# Sheet1.net
KiCad netlist of a schematic drawn in Altium Designer
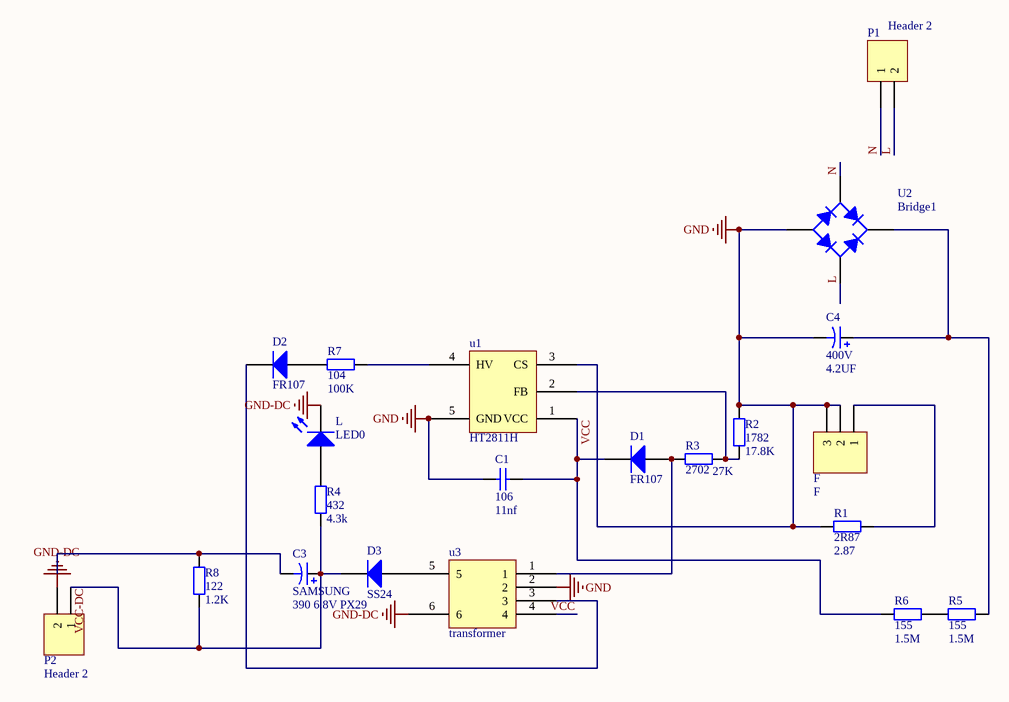
[diagram p0: Sheet1.SchDoc]

(export (version "E")
  (design (tool "Eeschema 10.0.6"))
  (components
    (comp (ref "C1")
      (value "106")
      (footprint "RAD-0.3")
      (description "Capacitor")
      (fields (field (name "ALTIUM_VALUE") "11nf") (field (name "PUBLISHER") "Altium Limited"))
      (libsource (lib "Miscellaneous Devices") (part "Cap"))
    )
    (comp (ref "C3")
      (value "SAMSUNG")
      (footprint "RB7.6-15")
      (description "Polarized Capacitor (Radial)")
      (fields (field (name "ALTIUM_VALUE") "390 6.8V PX29") (field (name "PUBLISHER") "Altium Limited"))
      (libsource (lib "Miscellaneous Devices") (part "Cap Pol1"))
    )
    (comp (ref "C4")
      (value "400V")
      (footprint "RB7.6-15")
      (description "Polarized Capacitor (Radial)")
      (fields (field (name "ALTIUM_VALUE") "4.2UF") (field (name "PUBLISHER") "Altium Limited"))
      (libsource (lib "Miscellaneous Devices") (part "Cap Pol1"))
    )
    (comp (ref "D1")
      (value "FR107")
      (footprint "LC-SOD-123F")
      (description "1 Amp General Purpose Rectifier")
      (fields (field (name "PUBLISHER") "Altium Limited"))
      (libsource (lib "Miscellaneous Devices") (part "Diode 1N4005"))
    )
    (comp (ref "D2")
      (value "FR107")
      (footprint "LC-SOD-123F")
      (description "1 Amp General Purpose Rectifier")
      (fields (field (name "PUBLISHER") "Altium Limited"))
      (libsource (lib "Miscellaneous Devices") (part "Diode 1N4005"))
    )
    (comp (ref "D3")
      (value "SS24")
      (footprint "LC-SMA(DO-214AC)_S1")
      (description "High Conductance Ultra Fast Diode")
      (fields (field (name "PUBLISHER") "Altium Limited"))
      (libsource (lib "Miscellaneous Devices") (part "Diode 1N4150"))
    )
    (comp (ref "F")
      (value "F")
      (footprint "HDR1X3")
      (description "Header, 3-Pin")
      (fields (field (name "PUBLISHER") "Altium Limited"))
      (libsource (lib "Miscellaneous Connectors") (part "Header 3"))
    )
    (comp (ref "L")
      (value "LED0")
      (footprint "LED-0")
      (description "Typical INFRARED GaAs LED")
      (fields (field (name "PUBLISHER") "Altium Limited"))
      (libsource (lib "Miscellaneous Devices") (part "LED0"))
    )
    (comp (ref "P1")
      (value "Header 2")
      (footprint "HDR1X2")
      (description "Header, 2-Pin")
      (fields (field (name "PUBLISHER") "Altium Limited"))
      (libsource (lib "") (part "Header 2_1"))
    )
    (comp (ref "P2")
      (value "Header 2")
      (footprint "HDR1X2")
      (description "Header, 2-Pin")
      (fields (field (name "PUBLISHER") "Altium Limited"))
      (libsource (lib "Miscellaneous Connectors") (part "Header 2"))
    )
    (comp (ref "R1")
      (value "2R87")
      (footprint "AXIAL-0.4")
      (description "Resistor")
      (fields (field (name "ALTIUM_VALUE") "2.87") (field (name "PUBLISHER") "Altium Limited"))
      (libsource (lib "") (part "Res2_1"))
    )
    (comp (ref "R2")
      (value "1782")
      (footprint "AXIAL-0.4")
      (description "Resistor")
      (fields (field (name "ALTIUM_VALUE") "17.8K") (field (name "PUBLISHER") "Altium Limited"))
      (libsource (lib "Miscellaneous Devices") (part "Res2"))
    )
    (comp (ref "R3")
      (value "2702")
      (footprint "AXIAL-0.4")
      (description "Resistor")
      (fields (field (name "ALTIUM_VALUE") "27K") (field (name "PUBLISHER") "Altium Limited"))
      (libsource (lib "") (part "Res2_3"))
    )
    (comp (ref "R4")
      (value "432")
      (footprint "AXIAL-0.4")
      (description "Resistor")
      (fields (field (name "ALTIUM_VALUE") "4.3k") (field (name "PUBLISHER") "Altium Limited"))
      (libsource (lib "Miscellaneous Devices") (part "Res2"))
    )
    (comp (ref "R5")
      (value "155")
      (footprint "AXIAL-0.4")
      (description "Resistor")
      (fields (field (name "ALTIUM_VALUE") "1.5M") (field (name "PUBLISHER") "Altium Limited"))
      (libsource (lib "") (part "Res2_1"))
    )
    (comp (ref "R6")
      (value "155")
      (footprint "AXIAL-0.4")
      (description "Resistor")
      (fields (field (name "ALTIUM_VALUE") "1.5M") (field (name "PUBLISHER") "Altium Limited"))
      (libsource (lib "") (part "Res2_1"))
    )
    (comp (ref "R7")
      (value "104")
      (footprint "AXIAL-0.4")
      (description "Resistor")
      (fields (field (name "ALTIUM_VALUE") "100K") (field (name "PUBLISHER") "Altium Limited"))
      (libsource (lib "") (part "Res2_1"))
    )
    (comp (ref "R8")
      (value "122")
      (footprint "AXIAL-0.4")
      (description "Resistor")
      (fields (field (name "ALTIUM_VALUE") "1.2K") (field (name "PUBLISHER") "Altium Limited"))
      (libsource (lib "") (part "Res2_2"))
    )
    (comp (ref "u1") (value "HT2811H") (libsource (lib "Schlib1") (part "HT2811H")))
    (comp (ref "U2")
      (value "Bridge1")
      (footprint "E-BIP-P4/D10")
      (description "Full Wave Diode Bridge")
      (fields (field (name "PUBLISHER") "Altium Limited"))
      (libsource (lib "Miscellaneous Devices") (part "Bridge1"))
    )
    (comp (ref "u3") (value "transformer") (libsource (lib "Schlib1") (part "transformer")))
  )
  (nets
    (net (code "1") (name "/L") (class "Default")
      (node (ref "P1") (pin "2") (pinfunction "2_2") (pintype "passive"))
      (node (ref "U2") (pin "2") (pinfunction "C_2") (pintype "passive"))
    )
    (net (code "2") (name "/N") (class "Default")
      (node (ref "P1") (pin "1") (pinfunction "1_1") (pintype "passive"))
      (node (ref "U2") (pin "4") (pinfunction "C_4") (pintype "passive"))
    )
    (net (code "3") (name "/VCC") (class "Default")
      (node (ref "C1") (pin "2") (pinfunction "2_2") (pintype "passive"))
      (node (ref "D1") (pin "2") (pinfunction "K_2") (pintype "passive"))
      (node (ref "R6") (pin "1") (pinfunction "1_1") (pintype "passive"))
      (node (ref "u1") (pin "1") (pinfunction "VCC_1") (pintype "passive"))
    )
    (net (code "4") (name "/VCC-DC") (class "Default")
      (node (ref "C3") (pin "1") (pinfunction "1_1") (pintype "passive"))
      (node (ref "D3") (pin "2") (pinfunction "K_2") (pintype "passive"))
      (node (ref "P2") (pin "1") (pinfunction "1_1") (pintype "passive"))
      (node (ref "R4") (pin "1") (pinfunction "1_1") (pintype "passive"))
      (node (ref "R8") (pin "2") (pinfunction "2_2") (pintype "passive"))
    )
    (net (code "5") (name "GND") (class "Default")
      (node (ref "C1") (pin "1") (pinfunction "1_1") (pintype "passive"))
      (node (ref "C4") (pin "2") (pinfunction "2_2") (pintype "passive"))
      (node (ref "F") (pin "2") (pinfunction "2_2") (pintype "passive"))
      (node (ref "F") (pin "3") (pinfunction "3_3") (pintype "passive"))
      (node (ref "R1") (pin "1") (pinfunction "1_1") (pintype "passive"))
      (node (ref "R2") (pin "2") (pinfunction "2_2") (pintype "passive"))
      (node (ref "U2") (pin "3") (pinfunction "A_3") (pintype "passive"))
      (node (ref "u1") (pin "3") (pinfunction "CS_3") (pintype "passive"))
      (node (ref "u1") (pin "5") (pinfunction "GND_5") (pintype "passive"))
      (node (ref "u3") (pin "2") (pinfunction "2_2") (pintype "passive"))
    )
    (net (code "6") (name "GND-DC") (class "Default")
      (node (ref "L") (pin "2") (pinfunction "K_2") (pintype "passive"))
      (node (ref "P2") (pin "2") (pinfunction "2_2") (pintype "passive"))
      (node (ref "u3") (pin "6") (pinfunction "6_6") (pintype "passive"))
    )
    (net (code "7") (name "Net-(C3-Pad2)") (class "Default")
      (node (ref "C3") (pin "2") (pinfunction "2_2") (pintype "passive"))
      (node (ref "R8") (pin "1") (pinfunction "1_1") (pintype "passive"))
    )
    (net (code "8") (name "Net-(D1-A)") (class "Default")
      (node (ref "D1") (pin "1") (pinfunction "A_1") (pintype "passive"))
      (node (ref "R3") (pin "2") (pinfunction "2_2") (pintype "passive"))
      (node (ref "u3") (pin "1") (pinfunction "1_1") (pintype "passive"))
    )
    (net (code "9") (name "Net-(D2-A)") (class "Default")
      (node (ref "D2") (pin "1") (pinfunction "A_1") (pintype "passive"))
      (node (ref "R7") (pin "1") (pinfunction "1_1") (pintype "passive"))
    )
    (net (code "10") (name "Net-(D2-K)") (class "Default")
      (node (ref "D2") (pin "2") (pinfunction "K_2") (pintype "passive"))
      (node (ref "u3") (pin "3") (pinfunction "3_3") (pintype "passive"))
    )
    (net (code "11") (name "Net-(D3-A)") (class "Default")
      (node (ref "D3") (pin "1") (pinfunction "A_1") (pintype "passive"))
      (node (ref "u3") (pin "5") (pinfunction "5_5") (pintype "passive"))
    )
    (net (code "12") (name "Net-(F-Pad1)") (class "Default")
      (node (ref "F") (pin "1") (pinfunction "1_1") (pintype "passive"))
      (node (ref "R1") (pin "2") (pinfunction "2_2") (pintype "passive"))
    )
    (net (code "13") (name "Net-(L-A)") (class "Default")
      (node (ref "L") (pin "1") (pinfunction "A_1") (pintype "passive"))
      (node (ref "R4") (pin "2") (pinfunction "2_2") (pintype "passive"))
    )
    (net (code "14") (name "Net-(R5-Pad1)") (class "Default")
      (node (ref "R5") (pin "1") (pinfunction "1_1") (pintype "passive"))
      (node (ref "R6") (pin "2") (pinfunction "2_2") (pintype "passive"))
    )
    (net (code "15") (name "Net-(U2-K)") (class "Default")
      (node (ref "C4") (pin "1") (pinfunction "1_1") (pintype "passive"))
      (node (ref "R5") (pin "2") (pinfunction "2_2") (pintype "passive"))
      (node (ref "U2") (pin "1") (pinfunction "K_1") (pintype "passive"))
    )
    (net (code "16") (name "Net-(u1-FB)") (class "Default")
      (node (ref "R2") (pin "1") (pinfunction "1_1") (pintype "passive"))
      (node (ref "R3") (pin "1") (pinfunction "1_1") (pintype "passive"))
      (node (ref "u1") (pin "2") (pinfunction "FB_2") (pintype "passive"))
    )
    (net (code "17") (name "Net-(u1-HV)") (class "Default")
      (node (ref "R7") (pin "2") (pinfunction "2_2") (pintype "passive"))
      (node (ref "u1") (pin "4") (pinfunction "HV_4") (pintype "passive"))
    )
    (net (code "18") (name "unconnected-(u3-Pad4)") (class "Default")
      (node (ref "u3") (pin "4") (pinfunction "4_4") (pintype "passive"))
    )
  )
)
